# Display_PWR.net
KiCad netlist of a schematic drawn in Altium Designer
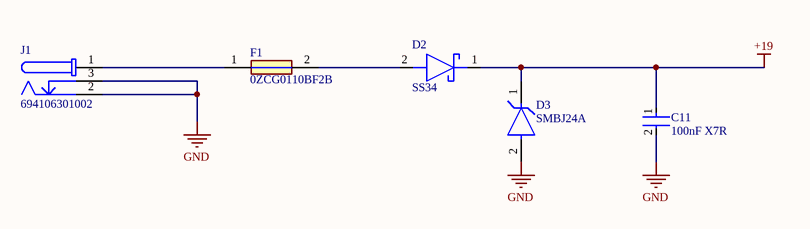
[diagram p0: Display_PWR.SchDoc]

(export (version "E")
  (design (tool "Eeschema 10.0.6"))
  (components
    (comp (ref "C11")
      (value "100nF X7R")
      (footprint "FP-CL10-IPC_C")
      (description "Cap Ceramic 100nF 25V X7R ±10% Pad SMD 0603 +125°C T/R")
      (fields (field (name "TOLERANCE") "10%"))
      (libsource (lib "Altium Content Vault") (part "b4654b650e69147ec39a6b967a45e02"))
    )
    (comp (ref "D2")
      (value "SS34")
      (footprint "SamacSys:DIOM8059X256N")
      (description "Schottky Diode")
      (fields (field (name "MOUSER PART NUMBER") "512-SS34"))
      (libsource (lib "*") (part "SS34"))
    )
    (comp (ref "D3")
      (value "SMBJ24A")
      (footprint "FP-SMBJ-MFG")
      (description "TVS DIODE 24V 38.9V SMB")
      (libsource (lib "Altium Content Vault") (part "f813f71cba58e380607f5dd3caf9714"))
    )
    (comp (ref "F1")
      (value "0ZCG0110BF2B")
      (footprint "SamacSys:FUSC4632X130N")
      (description "Fuse")
      (fields (field (name "MOUSER PART NUMBER") "530-0ZCG0110BF2B"))
      (libsource (lib "*") (part "0ZCG0110BF2B"))
    )
    (comp (ref "J1")
      (value "694106301002")
      (footprint "694106301002")
      (libsource (lib "Altium Content Vault") (part "DC Power Jack"))
    )
  )
  (nets
    (net (code "1") (name "+19") (class "Default")
      (node (ref "C11") (pin "1") (pinfunction "1_1") (pintype "passive"))
      (node (ref "D2") (pin "1") (pinfunction "K_1") (pintype "passive"))
      (node (ref "D3") (pin "1") (pinfunction "C_1") (pintype "passive"))
    )
    (net (code "2") (name "GND") (class "Default")
      (node (ref "C11") (pin "2") (pinfunction "2_2") (pintype "passive"))
      (node (ref "D3") (pin "2") (pinfunction "A_2") (pintype "passive"))
      (node (ref "J1") (pin "2") (pinfunction "2_2") (pintype "passive"))
      (node (ref "J1") (pin "3") (pinfunction "3_3") (pintype "passive"))
    )
    (net (code "3") (name "Net-(D2-A)") (class "Default")
      (node (ref "D2") (pin "2") (pinfunction "A_2") (pintype "passive"))
      (node (ref "F1") (pin "2") (pinfunction "2_2") (pintype "passive"))
    )
    (net (code "4") (name "Net-(F1-Pad1)") (class "Default")
      (node (ref "F1") (pin "1") (pinfunction "1_1") (pintype "passive"))
      (node (ref "J1") (pin "1") (pinfunction "1_1") (pintype "passive"))
    )
  )
)
